# PWM_v1_1.net
KiCad netlist of a schematic drawn in EAGLE
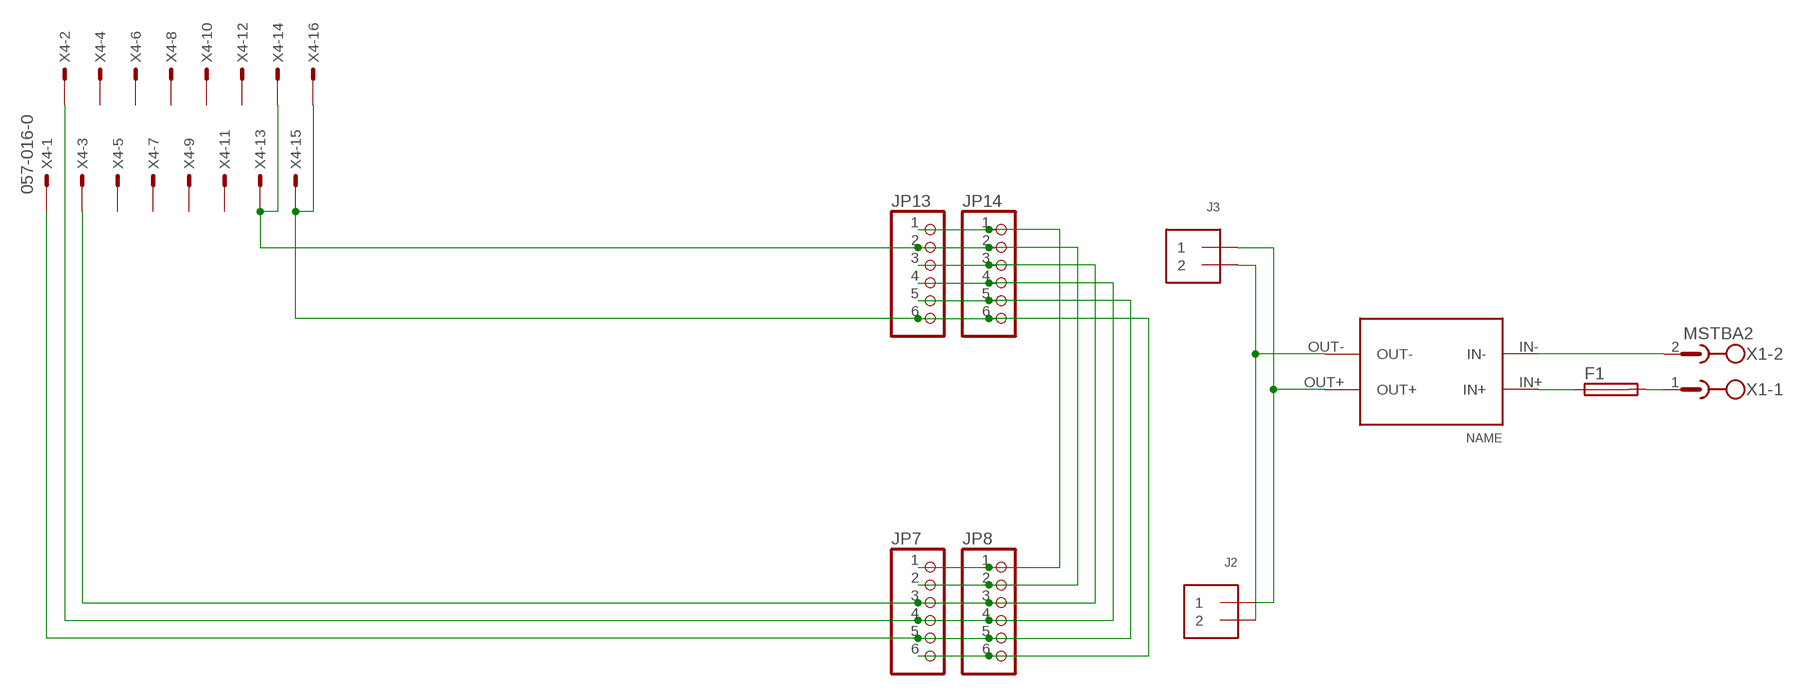
[diagram p0: schematic, sheet 1]

(export (version "E")
  (design (tool "Eeschema 10.0.6"))
  (components
    (comp (ref "F1")
      (value "SH25")
      (footprint "eagle-import:SH25")
      (fields (field (name "MF") "SCHURTER") (field (name "MPN") "0031.8211"))
      (libsource (lib "eagle-import") (part "SH25"))
    )
    (comp (ref "J2")
      (value "TERMBLOCK_1X2")
      (footprint "eagle-import:TERMBLOCK_1X2-3.5MM")
      (libsource (lib "eagle-import") (part "TERMBLOCK_1X2"))
    )
    (comp (ref "J3")
      (value "TERMBLOCK_1X2")
      (footprint "eagle-import:TERMBLOCK_1X2-3.5MM")
      (libsource (lib "eagle-import") (part "TERMBLOCK_1X2"))
    )
    (comp (ref "JP7")
      (value "PINHD-1X6CB")
      (footprint "eagle-import:1X06-CLEANBIG")
      (libsource (lib "eagle-import") (part "PINHD-1X6CB"))
    )
    (comp (ref "JP8")
      (value "PINHD-1X6CB")
      (footprint "eagle-import:1X06-CLEANBIG")
      (libsource (lib "eagle-import") (part "PINHD-1X6CB"))
    )
    (comp (ref "JP13")
      (value "PINHD-1X6CB")
      (footprint "eagle-import:1X06-CLEANBIG")
      (libsource (lib "eagle-import") (part "PINHD-1X6CB"))
    )
    (comp (ref "JP14")
      (value "PINHD-1X6CB")
      (footprint "eagle-import:1X06-CLEANBIG")
      (libsource (lib "eagle-import") (part "PINHD-1X6CB"))
    )
    (comp (ref "U$2")
      (value "CP8-ADJ")
      (footprint "eagle-import:CP8-ADJ")
      (libsource (lib "eagle-import") (part "CP8-ADJ"))
    )
    (comp (ref "X1")
      (value "MSTBA2")
      (footprint "eagle-import:MSTBA2")
      (fields (field (name "MF") "FARNELL") (field (name "MPN") "1757242"))
      (libsource (lib "eagle-import") (part "MSTBA2"))
    )
    (comp (ref "X4")
      (value "057-016-0")
      (footprint "eagle-import:057-016-0")
      (libsource (lib "eagle-import") (part "057-016-0"))
    )
  )
  (nets
    (net (code "1") (name "Net-(F1-Pad1)") (class "Default")
      (node (ref "F1") (pin "1") (pinfunction "1_1") (pintype "passive"))
      (node (ref "U$2") (pin "IN+") (pinfunction "IN+_IN+") (pintype "passive"))
    )
    (net (code "2") (name "Net-(F1-Pad2)") (class "Default")
      (node (ref "F1") (pin "2") (pinfunction "2_2") (pintype "passive"))
      (node (ref "X1") (pin "1") (pinfunction "1_1") (pintype "passive"))
    )
    (net (code "3") (name "Net-(J2-Pad1)") (class "Default")
      (node (ref "J2") (pin "1") (pinfunction "1_1") (pintype "passive"))
      (node (ref "J3") (pin "1") (pinfunction "1_1") (pintype "passive"))
      (node (ref "U$2") (pin "OUT+") (pinfunction "OUT+_OUT+") (pintype "passive"))
    )
    (net (code "4") (name "Net-(J2-Pad2)") (class "Default")
      (node (ref "J2") (pin "2") (pinfunction "2_2") (pintype "passive"))
      (node (ref "J3") (pin "2") (pinfunction "2_2") (pintype "passive"))
      (node (ref "U$2") (pin "OUT-") (pinfunction "OUT-_OUT-") (pintype "passive"))
    )
    (net (code "5") (name "Net-(JP13-Pad1)") (class "Default")
      (node (ref "JP13") (pin "1") (pinfunction "1_1") (pintype "passive"))
      (node (ref "JP14") (pin "1") (pinfunction "1_1") (pintype "passive"))
      (node (ref "JP7") (pin "1") (pinfunction "1_1") (pintype "passive"))
      (node (ref "JP8") (pin "1") (pinfunction "1_1") (pintype "passive"))
    )
    (net (code "6") (name "Net-(X1B-1)") (class "Default")
      (node (ref "U$2") (pin "IN-") (pinfunction "IN-_IN-") (pintype "passive"))
      (node (ref "X1") (pin "2") (pinfunction "1_2") (pintype "passive"))
    )
    (net (code "7") (name "Net-(X4A-S)") (class "Default")
      (node (ref "JP13") (pin "5") (pinfunction "5_5") (pintype "passive"))
      (node (ref "JP14") (pin "5") (pinfunction "5_5") (pintype "passive"))
      (node (ref "JP7") (pin "5") (pinfunction "5_5") (pintype "passive"))
      (node (ref "JP8") (pin "5") (pinfunction "5_5") (pintype "passive"))
      (node (ref "X4") (pin "1") (pinfunction "S_1") (pintype "passive"))
    )
    (net (code "8") (name "Net-(X4E-S)") (class "Default")
      (node (ref "JP13") (pin "2") (pinfunction "2_2") (pintype "passive"))
      (node (ref "JP14") (pin "2") (pinfunction "2_2") (pintype "passive"))
      (node (ref "JP7") (pin "2") (pinfunction "2_2") (pintype "passive"))
      (node (ref "JP8") (pin "2") (pinfunction "2_2") (pintype "passive"))
      (node (ref "X4") (pin "13") (pinfunction "S_13") (pintype "passive"))
      (node (ref "X4") (pin "14") (pinfunction "S_14") (pintype "passive"))
    )
    (net (code "9") (name "Net-(X4G-S)") (class "Default")
      (node (ref "JP13") (pin "6") (pinfunction "6_6") (pintype "passive"))
      (node (ref "JP14") (pin "6") (pinfunction "6_6") (pintype "passive"))
      (node (ref "JP7") (pin "6") (pinfunction "6_6") (pintype "passive"))
      (node (ref "JP8") (pin "6") (pinfunction "6_6") (pintype "passive"))
      (node (ref "X4") (pin "15") (pinfunction "S_15") (pintype "passive"))
      (node (ref "X4") (pin "16") (pinfunction "S_16") (pintype "passive"))
    )
    (net (code "10") (name "Net-(X4I-S)") (class "Default")
      (node (ref "JP13") (pin "4") (pinfunction "4_4") (pintype "passive"))
      (node (ref "JP14") (pin "4") (pinfunction "4_4") (pintype "passive"))
      (node (ref "JP7") (pin "4") (pinfunction "4_4") (pintype "passive"))
      (node (ref "JP8") (pin "4") (pinfunction "4_4") (pintype "passive"))
      (node (ref "X4") (pin "2") (pinfunction "S_2") (pintype "passive"))
    )
    (net (code "11") (name "Net-(X4J-S)") (class "Default")
      (node (ref "JP13") (pin "3") (pinfunction "3_3") (pintype "passive"))
      (node (ref "JP14") (pin "3") (pinfunction "3_3") (pintype "passive"))
      (node (ref "JP7") (pin "3") (pinfunction "3_3") (pintype "passive"))
      (node (ref "JP8") (pin "3") (pinfunction "3_3") (pintype "passive"))
      (node (ref "X4") (pin "3") (pinfunction "S_3") (pintype "passive"))
    )
    (net (code "12") (name "unconnected-(X4B-S-Pad10)") (class "Default")
      (node (ref "X4") (pin "10") (pinfunction "S_10") (pintype "passive"))
    )
    (net (code "13") (name "unconnected-(X4C-S-Pad11)") (class "Default")
      (node (ref "X4") (pin "11") (pinfunction "S_11") (pintype "passive"))
    )
    (net (code "14") (name "unconnected-(X4D-S-Pad12)") (class "Default")
      (node (ref "X4") (pin "12") (pinfunction "S_12") (pintype "passive"))
    )
    (net (code "15") (name "unconnected-(X4K-S-Pad4)") (class "Default")
      (node (ref "X4") (pin "4") (pinfunction "S_4") (pintype "passive"))
    )
    (net (code "16") (name "unconnected-(X4L-S-Pad5)") (class "Default")
      (node (ref "X4") (pin "5") (pinfunction "S_5") (pintype "passive"))
    )
    (net (code "17") (name "unconnected-(X4M-S-Pad6)") (class "Default")
      (node (ref "X4") (pin "6") (pinfunction "S_6") (pintype "passive"))
    )
    (net (code "18") (name "unconnected-(X4N-S-Pad7)") (class "Default")
      (node (ref "X4") (pin "7") (pinfunction "S_7") (pintype "passive"))
    )
    (net (code "19") (name "unconnected-(X4O-S-Pad8)") (class "Default")
      (node (ref "X4") (pin "8") (pinfunction "S_8") (pintype "passive"))
    )
    (net (code "20") (name "unconnected-(X4P-S-Pad9)") (class "Default")
      (node (ref "X4") (pin "9") (pinfunction "S_9") (pintype "passive"))
    )
  )
)
